# BusPirate-v5_0-SSOP.net
KiCad netlist of a schematic drawn in EAGLE
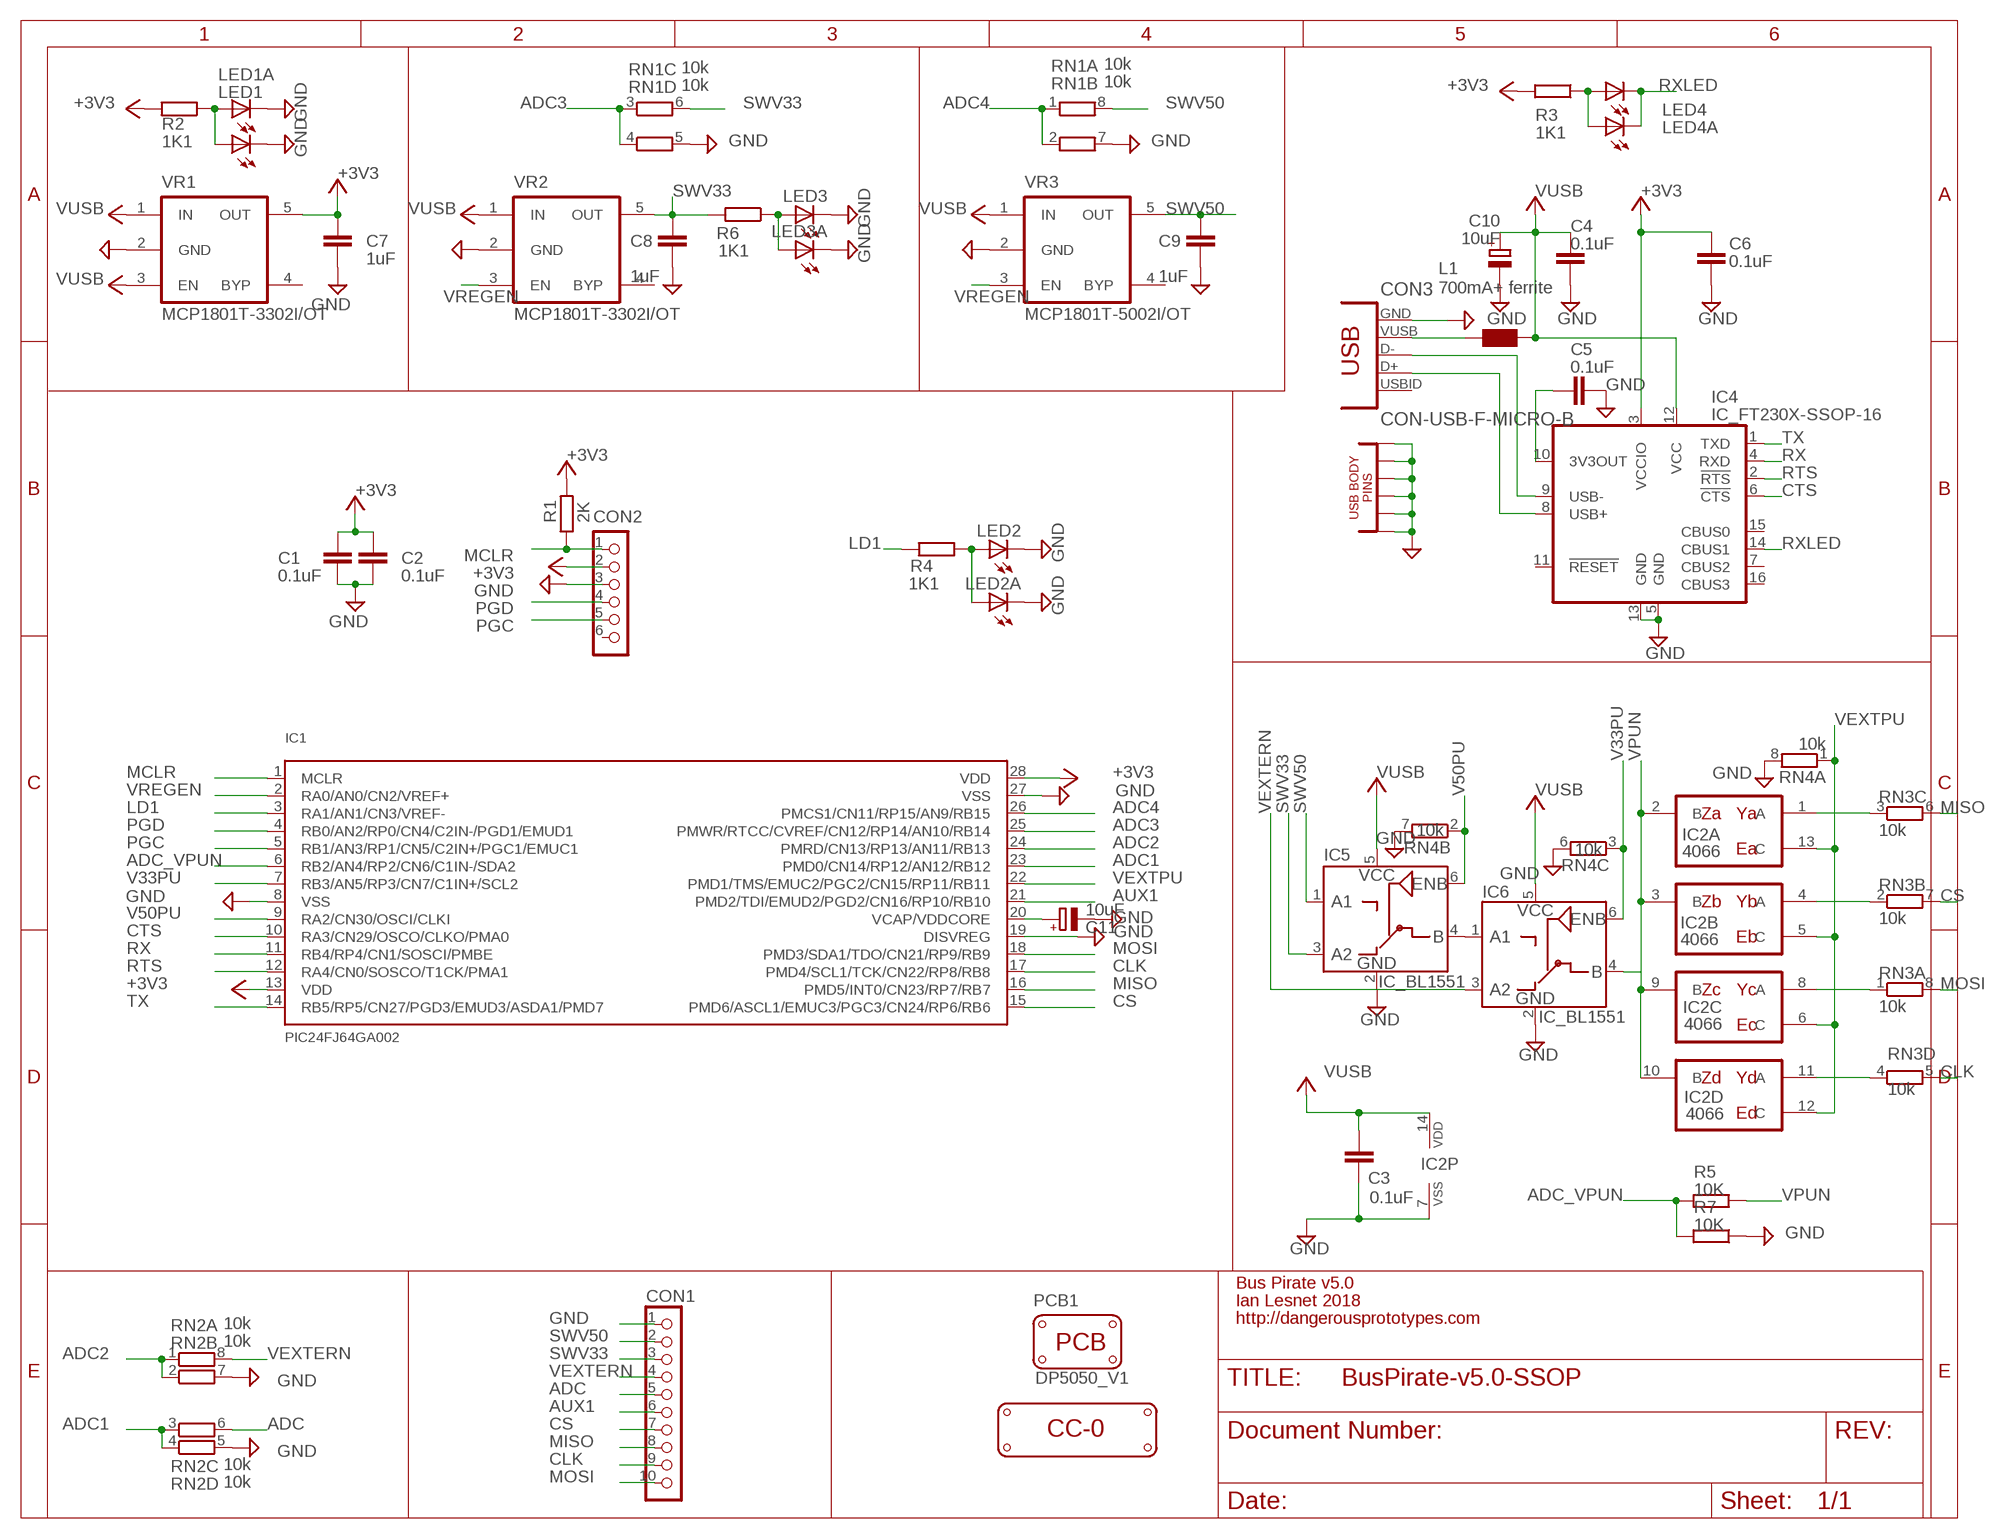
[diagram p0: schematic, sheet 1]

(export (version "E")
  (design (tool "Eeschema 10.0.6"))
  (components
    (comp (ref "C1")
      (value "0.1uF")
      (footprint "eagle-import:C603")
      (libsource (lib "eagle-import") (part "CAPC603"))
    )
    (comp (ref "C2")
      (value "0.1uF")
      (footprint "eagle-import:C603")
      (libsource (lib "eagle-import") (part "CAPC603"))
    )
    (comp (ref "C3")
      (value "0.1uF")
      (footprint "eagle-import:C603")
      (libsource (lib "eagle-import") (part "CAPC603"))
    )
    (comp (ref "C4")
      (value "0.1uF")
      (footprint "eagle-import:C603")
      (libsource (lib "eagle-import") (part "CAPC603"))
    )
    (comp (ref "C5")
      (value "0.1uF")
      (footprint "eagle-import:C603")
      (libsource (lib "eagle-import") (part "CAPC603"))
    )
    (comp (ref "C6")
      (value "0.1uF")
      (footprint "eagle-import:C603")
      (libsource (lib "eagle-import") (part "CAPC603"))
    )
    (comp (ref "C7")
      (value "1uF")
      (footprint "eagle-import:C603")
      (libsource (lib "eagle-import") (part "CAPC603"))
    )
    (comp (ref "C8")
      (value "1uF")
      (footprint "eagle-import:C603")
      (libsource (lib "eagle-import") (part "CAPC603"))
    )
    (comp (ref "C9")
      (value "1uF")
      (footprint "eagle-import:C603")
      (libsource (lib "eagle-import") (part "CAPC603"))
    )
    (comp (ref "C10")
      (value "10uF")
      (footprint "eagle-import:SMC_A")
      (libsource (lib "eagle-import") (part "CPOL-EUSMCA"))
    )
    (comp (ref "C11")
      (value "10uF")
      (footprint "eagle-import:SMC_A")
      (libsource (lib "eagle-import") (part "CPOL-EUSMCA"))
    )
    (comp (ref "CON1")
      (value "CON_HEADER_1X10-RIGHT_ANGLED_PTH_SHROUDED")
      (footprint "eagle-import:M1X10_MALE_RIGHT_ANGLES_PTH_SHROUDED")
      (libsource (lib "eagle-import") (part "CON_HEADER_1X10-RIGHT_ANGLED_PTH_SHROUDED"))
    )
    (comp (ref "CON2")
      (value "CON_HEADER_1X06-PTH")
      (footprint "eagle-import:M1X6")
      (libsource (lib "eagle-import") (part "CON_HEADER_1X06-PTH"))
    )
    (comp (ref "CON3")
      (value "CON-USB-F-MICRO-B")
      (footprint "eagle-import:CON_USB_MICRO-B-1-MD05SMXXX-01")
      (libsource (lib "eagle-import") (part "CON-USB-F-MICRO-B"))
    )
    (comp (ref "IC1")
      (value "PIC24FJ64GA002")
      (footprint "eagle-import:SSOP28")
      (libsource (lib "eagle-import") (part "PIC24FJ64GA002"))
    )
    (comp (ref "IC2")
      (value "4066")
      (footprint "eagle-import:TSSOP14")
      (libsource (lib "eagle-import") (part "4066"))
    )
    (comp (ref "IC4")
      (value "IC_FT230X-SSOP-16")
      (footprint "eagle-import:SSOP-16-FTDI")
      (libsource (lib "eagle-import") (part "IC_FT230X-SSOP-16"))
    )
    (comp (ref "IC5")
      (value "IC_BL1551")
      (footprint "eagle-import:SOT-363")
      (libsource (lib "eagle-import") (part "IC_BL1551"))
    )
    (comp (ref "IC6")
      (value "IC_BL1551")
      (footprint "eagle-import:SOT-363")
      (libsource (lib "eagle-import") (part "IC_BL1551"))
    )
    (comp (ref "L1")
      (value "700mA+ ferrite")
      (footprint "eagle-import:WE-KI_0805_B")
      (libsource (lib "eagle-import") (part "WE-KIL_0805"))
    )
    (comp (ref "LED1")
      (value "LED-0805")
      (footprint "eagle-import:LED-805")
      (libsource (lib "eagle-import") (part "LED-0805"))
    )
    (comp (ref "LED1A")
      (value "LED-0805")
      (footprint "eagle-import:LED-805")
      (libsource (lib "eagle-import") (part "LED-0805"))
    )
    (comp (ref "LED2")
      (value "LED-0805")
      (footprint "eagle-import:LED-805")
      (libsource (lib "eagle-import") (part "LED-0805"))
    )
    (comp (ref "LED2A")
      (value "LED-0805")
      (footprint "eagle-import:LED-805")
      (libsource (lib "eagle-import") (part "LED-0805"))
    )
    (comp (ref "LED3")
      (value "LED-0805")
      (footprint "eagle-import:LED-805")
      (libsource (lib "eagle-import") (part "LED-0805"))
    )
    (comp (ref "LED3A")
      (value "LED-0805")
      (footprint "eagle-import:LED-805")
      (libsource (lib "eagle-import") (part "LED-0805"))
    )
    (comp (ref "LED4")
      (value "LED-0805")
      (footprint "eagle-import:LED-805")
      (libsource (lib "eagle-import") (part "LED-0805"))
    )
    (comp (ref "LED4A")
      (value "LED-0805")
      (footprint "eagle-import:LED-805")
      (libsource (lib "eagle-import") (part "LED-0805"))
    )
    (comp (ref "LOGO1")
      (value "LOGO_CC-0")
      (footprint "eagle-import:LOGO_CC-0")
      (libsource (lib "eagle-import") (part "LOGO_CC-0"))
    )
    (comp (ref "PCB1")
      (value "PCB_DP_SQUARE-5X5")
      (footprint "eagle-import:DP5050_V1")
      (libsource (lib "eagle-import") (part "PCB_DP_SQUARE-5X5"))
    )
    (comp (ref "R1")
      (value "2K")
      (footprint "eagle-import:R603")
      (libsource (lib "eagle-import") (part "RESISTORR603"))
    )
    (comp (ref "R2")
      (value "1K1")
      (footprint "eagle-import:R603")
      (libsource (lib "eagle-import") (part "RESISTORR603"))
    )
    (comp (ref "R3")
      (value "1K1")
      (footprint "eagle-import:R603")
      (libsource (lib "eagle-import") (part "RESISTORR603"))
    )
    (comp (ref "R4")
      (value "1K1")
      (footprint "eagle-import:R603")
      (libsource (lib "eagle-import") (part "RESISTORR603"))
    )
    (comp (ref "R5")
      (value "10K")
      (footprint "eagle-import:R603")
      (libsource (lib "eagle-import") (part "RESISTORR603"))
    )
    (comp (ref "R6")
      (value "1K1")
      (footprint "eagle-import:R603")
      (libsource (lib "eagle-import") (part "RESISTORR603"))
    )
    (comp (ref "R7")
      (value "10K")
      (footprint "eagle-import:R603")
      (libsource (lib "eagle-import") (part "RESISTORR603"))
    )
    (comp (ref "RN1")
      (value "10k")
      (footprint "eagle-import:RN8P-4R-CRA06S")
      (libsource (lib "eagle-import") (part "RNETWORK"))
    )
    (comp (ref "RN2")
      (value "10k")
      (footprint "eagle-import:RN8P-4R-CRA06S")
      (libsource (lib "eagle-import") (part "RNETWORK"))
    )
    (comp (ref "RN3")
      (value "10k")
      (footprint "eagle-import:RN8P-4R-CRA06S")
      (libsource (lib "eagle-import") (part "RNETWORK"))
    )
    (comp (ref "RN4")
      (value "10k")
      (footprint "eagle-import:RN8P-4R-CRA06S")
      (libsource (lib "eagle-import") (part "RNETWORK"))
    )
    (comp (ref "VR1")
      (value "MCP1801T-3302I/OT")
      (footprint "eagle-import:SOT-23-5")
      (libsource (lib "eagle-import") (part "MIC5205"))
    )
    (comp (ref "VR2")
      (value "MCP1801T-3302I/OT")
      (footprint "eagle-import:SOT-23-5")
      (libsource (lib "eagle-import") (part "MIC5205"))
    )
    (comp (ref "VR3")
      (value "MCP1801T-5002I/OT")
      (footprint "eagle-import:SOT-23-5")
      (libsource (lib "eagle-import") (part "MIC5205"))
    )
  )
  (nets
    (net (code "1") (name "/ADC") (class "Default")
      (node (ref "CON1") (pin "5") (pinfunction "5_5") (pintype "passive"))
      (node (ref "RN2") (pin "6") (pinfunction "2_6") (pintype "passive"))
    )
    (net (code "2") (name "/ADC1") (class "Default")
      (node (ref "IC1") (pin "23") (pinfunction "PMD0/CN14/RP12/AN12/RB12_23") (pintype "bidirectional"))
      (node (ref "RN2") (pin "3") (pinfunction "1_3") (pintype "passive"))
      (node (ref "RN2") (pin "4") (pinfunction "1_4") (pintype "passive"))
    )
    (net (code "3") (name "/ADC2") (class "Default")
      (node (ref "IC1") (pin "24") (pinfunction "PMRD/CN13/RP13/AN11/RB13_24") (pintype "bidirectional"))
      (node (ref "RN2") (pin "1") (pinfunction "1_1") (pintype "passive"))
      (node (ref "RN2") (pin "2") (pinfunction "1_2") (pintype "passive"))
    )
    (net (code "4") (name "/ADC3") (class "Default")
      (node (ref "IC1") (pin "25") (pinfunction "PMWR/RTCC/CVREF/CN12/RP14/AN10/RB14_25") (pintype "bidirectional"))
      (node (ref "RN1") (pin "3") (pinfunction "1_3") (pintype "passive"))
      (node (ref "RN1") (pin "4") (pinfunction "1_4") (pintype "passive"))
    )
    (net (code "5") (name "/ADC4") (class "Default")
      (node (ref "IC1") (pin "26") (pinfunction "PMCS1/CN11/RP15/AN9/RB15_26") (pintype "bidirectional"))
      (node (ref "RN1") (pin "1") (pinfunction "1_1") (pintype "passive"))
      (node (ref "RN1") (pin "2") (pinfunction "1_2") (pintype "passive"))
    )
    (net (code "6") (name "/ADC_VPUN") (class "Default")
      (node (ref "IC1") (pin "6") (pinfunction "RB2/AN4/RP2/CN6/C1IN-/SDA2_6") (pintype "bidirectional"))
      (node (ref "R5") (pin "2") (pinfunction "2_2") (pintype "passive"))
      (node (ref "R7") (pin "2") (pinfunction "2_2") (pintype "passive"))
    )
    (net (code "7") (name "/AUX1") (class "Default")
      (node (ref "CON1") (pin "6") (pinfunction "6_6") (pintype "passive"))
      (node (ref "IC1") (pin "21") (pinfunction "PMD2/TDI/EMUD2/PGD2/CN16/RP10/RB10_21") (pintype "bidirectional"))
    )
    (net (code "8") (name "/CLK") (class "Default")
      (node (ref "CON1") (pin "9") (pinfunction "9_9") (pintype "passive"))
      (node (ref "IC1") (pin "17") (pinfunction "PMD4/SCL1/TCK/CN22/RP8/RB8_17") (pintype "bidirectional"))
      (node (ref "RN3") (pin "5") (pinfunction "2_5") (pintype "passive"))
    )
    (net (code "9") (name "/CS") (class "Default")
      (node (ref "CON1") (pin "7") (pinfunction "7_7") (pintype "passive"))
      (node (ref "IC1") (pin "15") (pinfunction "PMD6/ASCL1/EMUC3/PGC3/CN24/RP6/RB6_15") (pintype "bidirectional"))
      (node (ref "RN3") (pin "7") (pinfunction "2_7") (pintype "passive"))
    )
    (net (code "10") (name "/CTS") (class "Default")
      (node (ref "IC1") (pin "10") (pinfunction "RA3/CN29/OSCO/CLKO/PMA0_10") (pintype "bidirectional"))
      (node (ref "IC4") (pin "6") (pinfunction "~{CTS}_6") (pintype "bidirectional"))
    )
    (net (code "11") (name "/LD1") (class "Default")
      (node (ref "IC1") (pin "3") (pinfunction "RA1/AN1/CN3/VREF-_3") (pintype "bidirectional"))
      (node (ref "R4") (pin "2") (pinfunction "2_2") (pintype "passive"))
    )
    (net (code "12") (name "/MCLR") (class "Default")
      (node (ref "CON2") (pin "1") (pinfunction "1_1") (pintype "bidirectional"))
      (node (ref "IC1") (pin "1") (pinfunction "MCLR_1") (pintype "input"))
      (node (ref "R1") (pin "1") (pinfunction "1_1") (pintype "passive"))
    )
    (net (code "13") (name "/MISO") (class "Default")
      (node (ref "CON1") (pin "8") (pinfunction "8_8") (pintype "passive"))
      (node (ref "IC1") (pin "16") (pinfunction "PMD5/INT0/CN23/RP7/RB7_16") (pintype "bidirectional"))
      (node (ref "RN3") (pin "6") (pinfunction "2_6") (pintype "passive"))
    )
    (net (code "14") (name "/MOSI") (class "Default")
      (node (ref "CON1") (pin "10") (pinfunction "10_10") (pintype "passive"))
      (node (ref "IC1") (pin "18") (pinfunction "PMD3/SDA1/TDO/CN21/RP9/RB9_18") (pintype "bidirectional"))
      (node (ref "RN3") (pin "8") (pinfunction "2_8") (pintype "passive"))
    )
    (net (code "15") (name "/PGC") (class "Default")
      (node (ref "CON2") (pin "5") (pinfunction "5_5") (pintype "passive"))
      (node (ref "IC1") (pin "5") (pinfunction "RB1/AN3/RP1/CN5/C2IN+/PGC1/EMUC1_5") (pintype "bidirectional"))
    )
    (net (code "16") (name "/PGD") (class "Default")
      (node (ref "CON2") (pin "4") (pinfunction "4_4") (pintype "passive"))
      (node (ref "IC1") (pin "4") (pinfunction "RB0/AN2/RP0/CN4/C2IN-/PGD1/EMUD1_4") (pintype "bidirectional"))
    )
    (net (code "17") (name "/RTS") (class "Default")
      (node (ref "IC1") (pin "12") (pinfunction "RA4/CN0/SOSCO/T1CK/PMA1_12") (pintype "bidirectional"))
      (node (ref "IC4") (pin "2") (pinfunction "~{RTS}_2") (pintype "bidirectional"))
    )
    (net (code "18") (name "/RX") (class "Default")
      (node (ref "IC1") (pin "11") (pinfunction "RB4/RP4/CN1/SOSCI/PMBE_11") (pintype "bidirectional"))
      (node (ref "IC4") (pin "4") (pinfunction "RXD_4") (pintype "input"))
    )
    (net (code "19") (name "/RXLED") (class "Default")
      (node (ref "IC4") (pin "14") (pinfunction "CBUS1_14") (pintype "bidirectional"))
      (node (ref "LED4") (pin "C") (pinfunction "C_C") (pintype "passive"))
      (node (ref "LED4A") (pin "C") (pinfunction "C_C") (pintype "passive"))
    )
    (net (code "20") (name "/SWV33") (class "Default")
      (node (ref "C8") (pin "1") (pinfunction "1_1") (pintype "passive"))
      (node (ref "CON1") (pin "3") (pinfunction "3_3") (pintype "passive"))
      (node (ref "IC5") (pin "3") (pinfunction "A2_3") (pintype "input"))
      (node (ref "R6") (pin "2") (pinfunction "2_2") (pintype "passive"))
      (node (ref "RN1") (pin "6") (pinfunction "2_6") (pintype "passive"))
      (node (ref "VR2") (pin "5") (pinfunction "OUT_5") (pintype "bidirectional"))
    )
    (net (code "21") (name "/SWV50") (class "Default")
      (node (ref "C9") (pin "1") (pinfunction "1_1") (pintype "passive"))
      (node (ref "CON1") (pin "2") (pinfunction "2_2") (pintype "passive"))
      (node (ref "IC5") (pin "1") (pinfunction "A1_1") (pintype "input"))
      (node (ref "RN1") (pin "8") (pinfunction "2_8") (pintype "passive"))
      (node (ref "VR3") (pin "5") (pinfunction "OUT_5") (pintype "bidirectional"))
    )
    (net (code "22") (name "/TX") (class "Default")
      (node (ref "IC1") (pin "14") (pinfunction "RB5/RP5/CN27/PGD3/EMUD3/ASDA1/PMD7_14") (pintype "bidirectional"))
      (node (ref "IC4") (pin "1") (pinfunction "TXD_1") (pintype "output"))
    )
    (net (code "23") (name "/V33PU") (class "Default")
      (node (ref "IC1") (pin "7") (pinfunction "RB3/AN5/RP3/CN7/C1IN+/SCL2_7") (pintype "bidirectional"))
      (node (ref "IC6") (pin "6") (pinfunction "ENB_6") (pintype "input"))
      (node (ref "RN4") (pin "3") (pinfunction "1_3") (pintype "passive"))
    )
    (net (code "24") (name "/V50PU") (class "Default")
      (node (ref "IC1") (pin "9") (pinfunction "RA2/CN30/OSCI/CLKI_9") (pintype "bidirectional"))
      (node (ref "IC5") (pin "6") (pinfunction "ENB_6") (pintype "input"))
      (node (ref "RN4") (pin "2") (pinfunction "1_2") (pintype "passive"))
    )
    (net (code "25") (name "/VEXTERN") (class "Default")
      (node (ref "CON1") (pin "4") (pinfunction "4_4") (pintype "passive"))
      (node (ref "IC6") (pin "3") (pinfunction "A2_3") (pintype "input"))
      (node (ref "RN2") (pin "8") (pinfunction "2_8") (pintype "passive"))
    )
    (net (code "26") (name "/VEXTPU") (class "Default")
      (node (ref "IC1") (pin "22") (pinfunction "PMD1/TMS/EMUC2/PGC2/CN15/RP11/RB11_22") (pintype "bidirectional"))
      (node (ref "IC2") (pin "12") (pinfunction "C_12") (pintype "input"))
      (node (ref "IC2") (pin "13") (pinfunction "C_13") (pintype "input"))
      (node (ref "IC2") (pin "5") (pinfunction "C_5") (pintype "input"))
      (node (ref "IC2") (pin "6") (pinfunction "C_6") (pintype "input"))
      (node (ref "RN4") (pin "1") (pinfunction "1_1") (pintype "passive"))
    )
    (net (code "27") (name "/VPUN") (class "Default")
      (node (ref "IC2") (pin "10") (pinfunction "B_10") (pintype "tri_state"))
      (node (ref "IC2") (pin "2") (pinfunction "B_2") (pintype "tri_state"))
      (node (ref "IC2") (pin "3") (pinfunction "B_3") (pintype "tri_state"))
      (node (ref "IC2") (pin "9") (pinfunction "B_9") (pintype "tri_state"))
      (node (ref "IC6") (pin "4") (pinfunction "B_4") (pintype "output"))
      (node (ref "R5") (pin "1") (pinfunction "1_1") (pintype "passive"))
    )
    (net (code "28") (name "/VREGEN") (class "Default")
      (node (ref "IC1") (pin "2") (pinfunction "RA0/AN0/CN2/VREF+_2") (pintype "bidirectional"))
      (node (ref "VR2") (pin "3") (pinfunction "EN_3") (pintype "bidirectional"))
      (node (ref "VR3") (pin "3") (pinfunction "EN_3") (pintype "bidirectional"))
    )
    (net (code "29") (name "GND") (class "Default")
      (node (ref "C1") (pin "2") (pinfunction "2_2") (pintype "passive"))
      (node (ref "C10") (pin "-") (pinfunction "-_-") (pintype "passive"))
      (node (ref "C11") (pin "-") (pinfunction "-_-") (pintype "passive"))
      (node (ref "C2") (pin "2") (pinfunction "2_2") (pintype "passive"))
      (node (ref "C3") (pin "2") (pinfunction "2_2") (pintype "passive"))
      (node (ref "C4") (pin "2") (pinfunction "2_2") (pintype "passive"))
      (node (ref "C5") (pin "2") (pinfunction "2_2") (pintype "passive"))
      (node (ref "C6") (pin "2") (pinfunction "2_2") (pintype "passive"))
      (node (ref "C7") (pin "2") (pinfunction "2_2") (pintype "passive"))
      (node (ref "C8") (pin "2") (pinfunction "2_2") (pintype "passive"))
      (node (ref "C9") (pin "2") (pinfunction "2_2") (pintype "passive"))
      (node (ref "CON1") (pin "1") (pinfunction "1_1") (pintype "passive"))
      (node (ref "CON2") (pin "3") (pinfunction "3_3") (pintype "passive"))
      (node (ref "CON3") (pin "GND1") (pinfunction "P$1_GND1") (pintype "passive"))
      (node (ref "CON3") (pin "GND2") (pinfunction "P$2_GND2") (pintype "passive"))
      (node (ref "CON3") (pin "GND3") (pinfunction "P$3_GND3") (pintype "passive"))
      (node (ref "CON3") (pin "GND4") (pinfunction "P$4_GND4") (pintype "passive"))
      (node (ref "CON3") (pin "GND5") (pinfunction "P$5_GND5") (pintype "passive"))
      (node (ref "CON3") (pin "GND6") (pinfunction "P$6_GND6") (pintype "passive"))
      (node (ref "CON3") (pin "P5") (pinfunction "GND_P5") (pintype "bidirectional"))
      (node (ref "IC1") (pin "19") (pinfunction "DISVREG_19") (pintype "power_in"))
      (node (ref "IC1") (pin "27") (pinfunction "VSS_27") (pintype "power_in"))
      (node (ref "IC1") (pin "8") (pinfunction "VSS_8") (pintype "power_in"))
      (node (ref "IC2") (pin "7") (pinfunction "VSS_7") (pintype "power_in"))
      (node (ref "IC4") (pin "13") (pinfunction "GND_13") (pintype "power_in"))
      (node (ref "IC4") (pin "5") (pinfunction "GND_5") (pintype "power_in"))
      (node (ref "IC5") (pin "2") (pinfunction "GND_2") (pintype "power_in"))
      (node (ref "IC6") (pin "2") (pinfunction "GND_2") (pintype "power_in"))
      (node (ref "LED1") (pin "C") (pinfunction "C_C") (pintype "passive"))
      (node (ref "LED1A") (pin "C") (pinfunction "C_C") (pintype "passive"))
      (node (ref "LED2") (pin "C") (pinfunction "C_C") (pintype "passive"))
      (node (ref "LED2A") (pin "C") (pinfunction "C_C") (pintype "passive"))
      (node (ref "LED3") (pin "C") (pinfunction "C_C") (pintype "passive"))
      (node (ref "LED3A") (pin "C") (pinfunction "C_C") (pintype "passive"))
      (node (ref "R7") (pin "1") (pinfunction "1_1") (pintype "passive"))
      (node (ref "RN1") (pin "5") (pinfunction "2_5") (pintype "passive"))
      (node (ref "RN1") (pin "7") (pinfunction "2_7") (pintype "passive"))
      (node (ref "RN2") (pin "5") (pinfunction "2_5") (pintype "passive"))
      (node (ref "RN2") (pin "7") (pinfunction "2_7") (pintype "passive"))
      (node (ref "RN4") (pin "6") (pinfunction "2_6") (pintype "passive"))
      (node (ref "RN4") (pin "7") (pinfunction "2_7") (pintype "passive"))
      (node (ref "RN4") (pin "8") (pinfunction "2_8") (pintype "passive"))
      (node (ref "VR1") (pin "2") (pinfunction "GND_2") (pintype "bidirectional"))
      (node (ref "VR2") (pin "2") (pinfunction "GND_2") (pintype "bidirectional"))
      (node (ref "VR3") (pin "2") (pinfunction "GND_2") (pintype "bidirectional"))
    )
    (net (code "30") (name "Net-(CON3A-D+)") (class "Default")
      (node (ref "CON3") (pin "P3") (pinfunction "D+_P3") (pintype "bidirectional"))
      (node (ref "IC4") (pin "8") (pinfunction "USB+_8") (pintype "output"))
    )
    (net (code "31") (name "Net-(CON3A-D-)") (class "Default")
      (node (ref "CON3") (pin "P2") (pinfunction "D-_P2") (pintype "bidirectional"))
      (node (ref "IC4") (pin "9") (pinfunction "USB-_9") (pintype "input"))
    )
    (net (code "32") (name "Net-(CON3A-VUSB)") (class "Default")
      (node (ref "CON3") (pin "P1") (pinfunction "VUSB_P1") (pintype "bidirectional"))
      (node (ref "L1") (pin "2") (pinfunction "1_2") (pintype "passive"))
    )
    (net (code "33") (name "Net-(IC1-VCAP{slash}VDDCORE)") (class "Default")
      (node (ref "C11") (pin "+") (pinfunction "+_+") (pintype "passive"))
      (node (ref "IC1") (pin "20") (pinfunction "VCAP/VDDCORE_20") (pintype "power_in"))
    )
    (net (code "34") (name "Net-(IC2A-A)") (class "Default")
      (node (ref "IC2") (pin "1") (pinfunction "A_1") (pintype "tri_state"))
      (node (ref "RN3") (pin "3") (pinfunction "1_3") (pintype "passive"))
    )
    (net (code "35") (name "Net-(IC2B-A)") (class "Default")
      (node (ref "IC2") (pin "4") (pinfunction "A_4") (pintype "tri_state"))
      (node (ref "RN3") (pin "2") (pinfunction "1_2") (pintype "passive"))
    )
    (net (code "36") (name "Net-(IC2C-A)") (class "Default")
      (node (ref "IC2") (pin "8") (pinfunction "A_8") (pintype "tri_state"))
      (node (ref "RN3") (pin "1") (pinfunction "1_1") (pintype "passive"))
    )
    (net (code "37") (name "Net-(IC2D-A)") (class "Default")
      (node (ref "IC2") (pin "11") (pinfunction "A_11") (pintype "tri_state"))
      (node (ref "RN3") (pin "4") (pinfunction "1_4") (pintype "passive"))
    )
    (net (code "38") (name "Net-(IC4-3V3OUT)") (class "Default")
      (node (ref "C5") (pin "1") (pinfunction "1_1") (pintype "passive"))
      (node (ref "IC4") (pin "10") (pinfunction "3V3OUT_10") (pintype "power_in"))
    )
    (net (code "39") (name "Net-(IC5-B)") (class "Default")
      (node (ref "IC5") (pin "4") (pinfunction "B_4") (pintype "output"))
      (node (ref "IC6") (pin "1") (pinfunction "A1_1") (pintype "input"))
    )
    (net (code "40") (name "Net-(LED1-PadA)") (class "Default")
      (node (ref "LED1") (pin "A") (pinfunction "A_A") (pintype "passive"))
      (node (ref "LED1A") (pin "A") (pinfunction "A_A") (pintype "passive"))
      (node (ref "R2") (pin "1") (pinfunction "1_1") (pintype "passive"))
    )
    (net (code "41") (name "Net-(LED2-PadA)") (class "Default")
      (node (ref "LED2") (pin "A") (pinfunction "A_A") (pintype "passive"))
      (node (ref "LED2A") (pin "A") (pinfunction "A_A") (pintype "passive"))
      (node (ref "R4") (pin "1") (pinfunction "1_1") (pintype "passive"))
    )
    (net (code "42") (name "Net-(LED3-PadA)") (class "Default")
      (node (ref "LED3") (pin "A") (pinfunction "A_A") (pintype "passive"))
      (node (ref "LED3A") (pin "A") (pinfunction "A_A") (pintype "passive"))
      (node (ref "R6") (pin "1") (pinfunction "1_1") (pintype "passive"))
    )
    (net (code "43") (name "Net-(LED4-PadA)") (class "Default")
      (node (ref "LED4") (pin "A") (pinfunction "A_A") (pintype "passive"))
      (node (ref "LED4A") (pin "A") (pinfunction "A_A") (pintype "passive"))
      (node (ref "R3") (pin "1") (pinfunction "1_1") (pintype "passive"))
    )
    (net (code "44") (name "SUPPLY_+3V3") (class "Default")
      (node (ref "C1") (pin "1") (pinfunction "1_1") (pintype "passive"))
      (node (ref "C2") (pin "1") (pinfunction "1_1") (pintype "passive"))
      (node (ref "C6") (pin "1") (pinfunction "1_1") (pintype "passive"))
      (node (ref "C7") (pin "1") (pinfunction "1_1") (pintype "passive"))
      (node (ref "CON2") (pin "2") (pinfunction "2_2") (pintype "bidirectional"))
      (node (ref "IC1") (pin "13") (pinfunction "VDD_13") (pintype "power_in"))
      (node (ref "IC1") (pin "28") (pinfunction "VDD_28") (pintype "power_in"))
      (node (ref "IC4") (pin "3") (pinfunction "VCCIO_3") (pintype "power_in"))
      (node (ref "R1") (pin "2") (pinfunction "2_2") (pintype "passive"))
      (node (ref "R2") (pin "2") (pinfunction "2_2") (pintype "passive"))
      (node (ref "R3") (pin "2") (pinfunction "2_2") (pintype "passive"))
      (node (ref "VR1") (pin "5") (pinfunction "OUT_5") (pintype "bidirectional"))
    )
    (net (code "45") (name "SUPPLY_VUSB") (class "Default")
      (node (ref "C10") (pin "+") (pinfunction "+_+") (pintype "passive"))
      (node (ref "C3") (pin "1") (pinfunction "1_1") (pintype "passive"))
      (node (ref "C4") (pin "1") (pinfunction "1_1") (pintype "passive"))
      (node (ref "IC2") (pin "14") (pinfunction "VDD_14") (pintype "power_in"))
      (node (ref "IC4") (pin "12") (pinfunction "VCC_12") (pintype "power_in"))
      (node (ref "IC5") (pin "5") (pinfunction "VCC_5") (pintype "power_in"))
      (node (ref "IC6") (pin "5") (pinfunction "VCC_5") (pintype "power_in"))
      (node (ref "L1") (pin "1") (pinfunction "2_1") (pintype "passive"))
      (node (ref "VR1") (pin "1") (pinfunction "IN_1") (pintype "bidirectional"))
      (node (ref "VR1") (pin "3") (pinfunction "EN_3") (pintype "bidirectional"))
      (node (ref "VR2") (pin "1") (pinfunction "IN_1") (pintype "bidirectional"))
      (node (ref "VR3") (pin "1") (pinfunction "IN_1") (pintype "bidirectional"))
    )
    (net (code "46") (name "unconnected-(CON2-Pad6)") (class "Default")
      (node (ref "CON2") (pin "6") (pinfunction "6_6") (pintype "passive"))
    )
    (net (code "47") (name "unconnected-(CON3A-USBID-PadP4)") (class "Default")
      (node (ref "CON3") (pin "P4") (pinfunction "USBID_P4") (pintype "bidirectional"))
    )
    (net (code "48") (name "unconnected-(IC4-CBUS0-Pad15)") (class "Default")
      (node (ref "IC4") (pin "15") (pinfunction "CBUS0_15") (pintype "bidirectional"))
    )
    (net (code "49") (name "unconnected-(IC4-CBUS2-Pad7)") (class "Default")
      (node (ref "IC4") (pin "7") (pinfunction "CBUS2_7") (pintype "bidirectional"))
    )
    (net (code "50") (name "unconnected-(IC4-CBUS3-Pad16)") (class "Default")
      (node (ref "IC4") (pin "16") (pinfunction "CBUS3_16") (pintype "bidirectional"))
    )
    (net (code "51") (name "unconnected-(IC4-~{RESET}-Pad11)") (class "Default")
      (node (ref "IC4") (pin "11") (pinfunction "~{RESET}_11") (pintype "bidirectional"))
    )
    (net (code "52") (name "unconnected-(VR1-BYP-Pad4)") (class "Default")
      (node (ref "VR1") (pin "4") (pinfunction "BYP_4") (pintype "bidirectional"))
    )
    (net (code "53") (name "unconnected-(VR2-BYP-Pad4)") (class "Default")
      (node (ref "VR2") (pin "4") (pinfunction "BYP_4") (pintype "bidirectional"))
    )
    (net (code "54") (name "unconnected-(VR3-BYP-Pad4)") (class "Default")
      (node (ref "VR3") (pin "4") (pinfunction "BYP_4") (pintype "bidirectional"))
    )
  )
)
